# PWM_PPM_FMU3_REV_G.net
KiCad netlist of a schematic drawn in Altium Designer
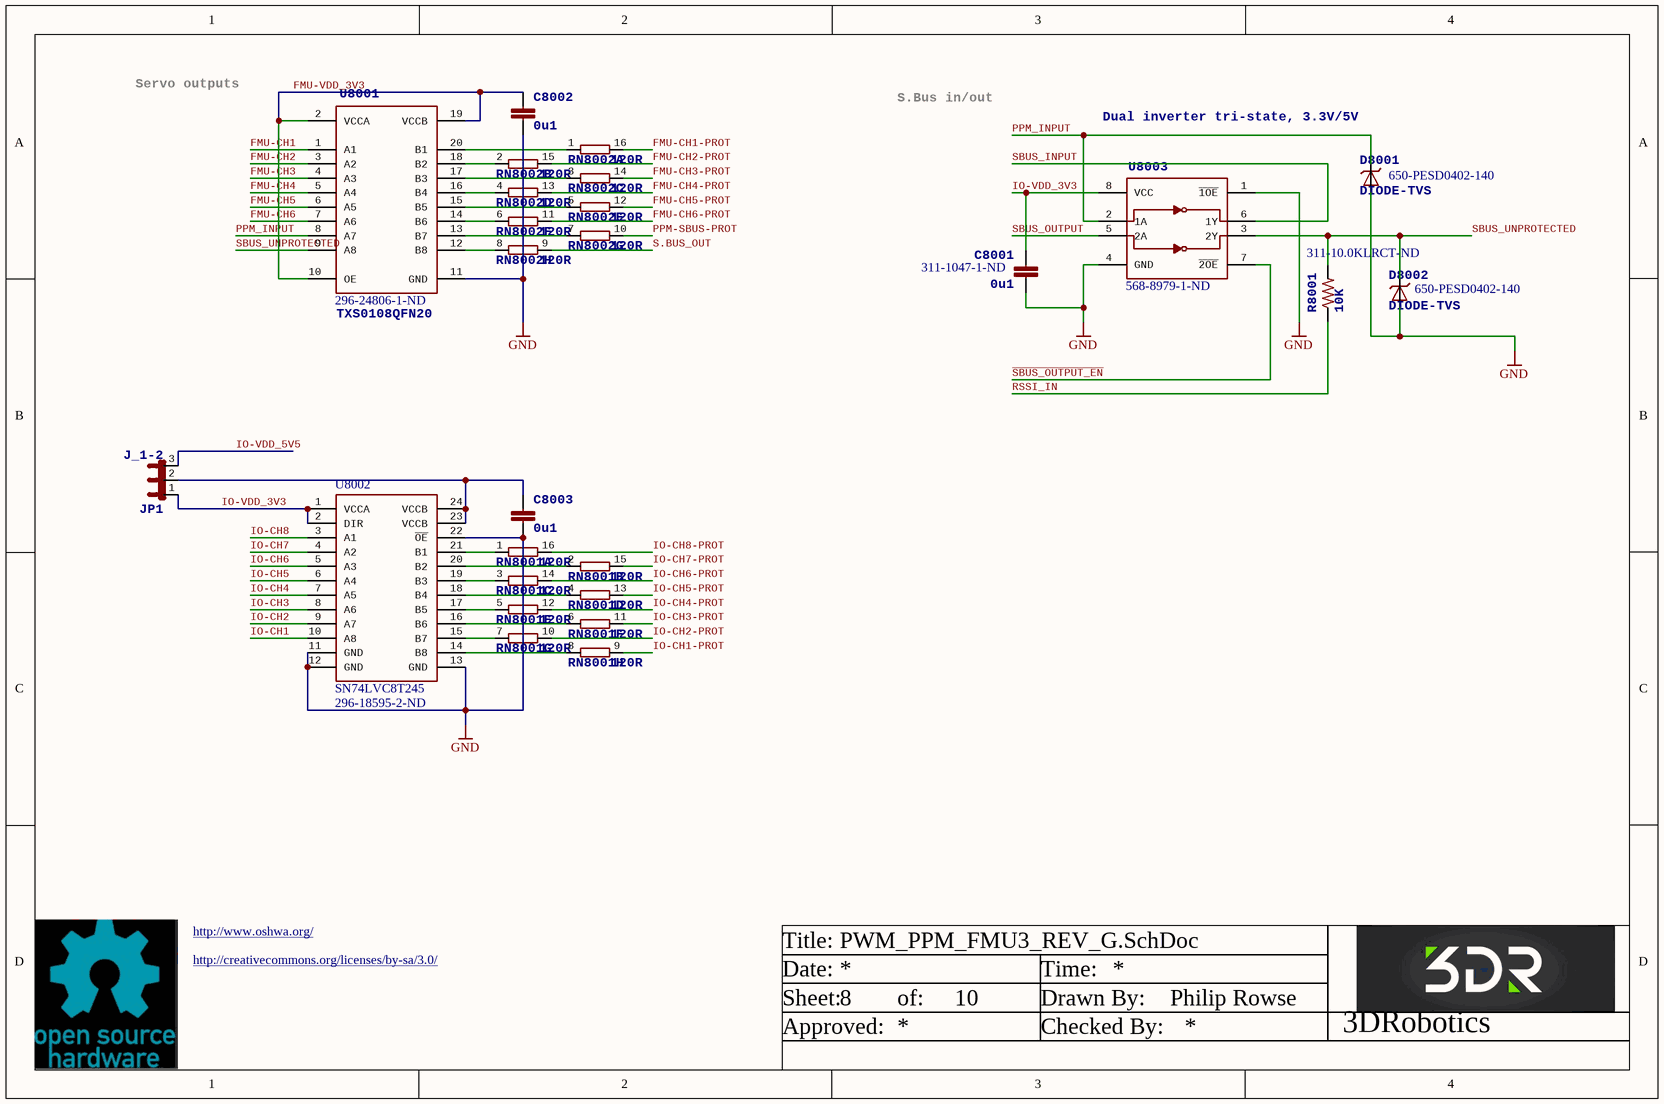
[diagram p0: PWM_PPM_FMU3_REV_G.SchDoc]

(export (version "E")
  (design (tool "Eeschema 10.0.6"))
  (components
    (comp (ref "C8001")
      (value "0u1")
      (footprint "0402-CAP")
      (description "CAP CER 0.1UF 16V Y5V 0402")
      (fields
        (field (name "PARTNO") "CC0402ZRY5V7BB104")
        (field (name "SUPPLIER PART NUMBER 1") "311-1047-1-ND")
        (field (name "3DR_PARTNO") "ECM0700")
      )
      (libsource (lib "") (part "CAP0402_1"))
    )
    (comp (ref "C8002")
      (value "0u1")
      (footprint "0402-CAP")
      (description "CAP CER 0.1UF 16V Y5V 0402")
      (fields (field (name "PARTNO") "CC0402ZRY5V7BB104") (field (name "3DR_PARTNO") "ECM0700"))
      (libsource (lib "pixhawk2") (part "CAP0402"))
    )
    (comp (ref "C8003")
      (value "0u1")
      (footprint "0402-CAP")
      (description "CAP CER 0.1UF 16V Y5V 0402")
      (fields (field (name "PARTNO") "CC0402ZRY5V7BB104") (field (name "3DR_PARTNO") "ECM0700"))
      (libsource (lib "pixhawk2") (part "CAP0402"))
    )
    (comp (ref "D8001")
      (value "DIODE-TVS")
      (footprint "0402-TVS")
      (description "TVS DIODE 14VWM 40VC 0402")
      (fields
        (field (name "SUPPLIER PART NUMBER 1") "650-PESD0402-140")
        (field (name "3DR_PARTNO") "ECM0837")
        (field (name "PARTNO") "PESD0402-140")
      )
      (libsource (lib "pixhawk2") (part "DIODE-TVS"))
    )
    (comp (ref "D8002")
      (value "DIODE-TVS")
      (footprint "0402-TVS")
      (description "TVS DIODE 14VWM 40VC 0402")
      (fields
        (field (name "SUPPLIER PART NUMBER 1") "650-PESD0402-140")
        (field (name "3DR_PARTNO") "ECM0837")
        (field (name "PARTNO") "PESD0402-140")
      )
      (libsource (lib "pixhawk2") (part "DIODE-TVS"))
    )
    (comp (ref "JP1")
      (value "J_1-2")
      (footprint "SJ_3_NO_PLACE_1-2_short")
      (libsource (lib "3DR") (part "JUMPER-31-2"))
    )
    (comp (ref "R8001")
      (value "10K")
      (footprint "0402-RES")
      (description "RES 10K OHM 1/16W 1% 0402 SMD")
      (fields
        (field (name "PARTNO") "RC0402FR-0710KL")
        (field (name "SUPPLIER PART NUMBER 1") "311-10.0KLRCT-ND")
        (field (name "3DR_PARTNO") "ECM0800")
      )
      (libsource (lib "pixhawk2") (part "RESISTOR0402-RES"))
    )
    (comp (ref "RN8001")
      (value "120R")
      (footprint "EXB2HV")
      (description "RES ARRAY 120 OHM 8 RES 1506")
      (fields (field (name "PARTNO") "EXB-2HV121JV") (field (name "3DR_PARTNO") "ECM0266"))
      (libsource (lib "pixhawk2") (part "8R-NEXB2HV-220R"))
    )
    (comp (ref "RN8002")
      (value "120R")
      (footprint "EXB2HV")
      (description "RES ARRAY 120 OHM 8 RES 1506")
      (fields (field (name "PARTNO") "EXB-2HV121JV") (field (name "3DR_PARTNO") "ECM0266"))
      (libsource (lib "pixhawk2") (part "8R-NEXB2HV-220R"))
    )
    (comp (ref "U8001")
      (value "TXS0108QFN20")
      (footprint "QFN20-RGY")
      (description "IC XLATR VOLT-LVL 8B BDIR 20QFN")
      (fields
        (field (name "SUPPLIER PART NUMBER 1") "296-24806-1-ND")
        (field (name "3DR_PARTNO") "ECM0845")
        (field (name "PARTNO") "TXS0108ERGYR")
      )
      (libsource (lib "pixhawk2") (part "TXS0108QFN20"))
    )
    (comp (ref "U8002")
      (value "SN74LVC8T245")
      (footprint "QFN20-RGY")
      (fields (field (name "SUPPLIER PART NUMBER 1") "296-18595-2-ND"))
      (libsource (lib "3DR") (part "SN74LVC8T245"))
    )
    (comp (ref "U8003")
      (value "Dual inverter tri-state, 3.3V/5V")
      (footprint "TSSOP8_SOT505-2")
      (description "IC INVERTER DUAL 4-INPUT 8TSSOP")
      (fields
        (field (name "SUPPLIER PART NUMBER 1") "568-8979-1-ND")
        (field (name "3DR_PARTNO") "ECM0817")
        (field (name "PARTNO") "74LVC2G240DP,125")
      )
      (libsource (lib "pixhawk2") (part "74LVC2G240-TSSOP-8"))
    )
  )
  (nets
    (net (code "1") (name "/FMU-CH1") (class "Default")
      (node (ref "U8001") (pin "1") (pinfunction "A1_1") (pintype "passive"))
    )
    (net (code "2") (name "/FMU-CH1-PROT") (class "Default")
      (node (ref "RN8002") (pin "16") (pinfunction "2_16") (pintype "passive"))
    )
    (net (code "3") (name "/FMU-CH2") (class "Default")
      (node (ref "U8001") (pin "3") (pinfunction "A2_3") (pintype "passive"))
    )
    (net (code "4") (name "/FMU-CH2-PROT") (class "Default")
      (node (ref "RN8002") (pin "15") (pinfunction "2_15") (pintype "passive"))
    )
    (net (code "5") (name "/FMU-CH3") (class "Default")
      (node (ref "U8001") (pin "4") (pinfunction "A3_4") (pintype "passive"))
    )
    (net (code "6") (name "/FMU-CH3-PROT") (class "Default")
      (node (ref "RN8002") (pin "14") (pinfunction "2_14") (pintype "passive"))
    )
    (net (code "7") (name "/FMU-CH4") (class "Default")
      (node (ref "U8001") (pin "5") (pinfunction "A4_5") (pintype "passive"))
    )
    (net (code "8") (name "/FMU-CH4-PROT") (class "Default")
      (node (ref "RN8002") (pin "13") (pinfunction "2_13") (pintype "passive"))
    )
    (net (code "9") (name "/FMU-CH5") (class "Default")
      (node (ref "U8001") (pin "6") (pinfunction "A5_6") (pintype "passive"))
    )
    (net (code "10") (name "/FMU-CH5-PROT") (class "Default")
      (node (ref "RN8002") (pin "12") (pinfunction "2_12") (pintype "passive"))
    )
    (net (code "11") (name "/FMU-CH6") (class "Default")
      (node (ref "U8001") (pin "7") (pinfunction "A6_7") (pintype "passive"))
    )
    (net (code "12") (name "/FMU-CH6-PROT") (class "Default")
      (node (ref "RN8002") (pin "11") (pinfunction "2_11") (pintype "passive"))
    )
    (net (code "13") (name "/FMU-VDD_3V3") (class "Default")
      (node (ref "C8002") (pin "P$1") (pinfunction "1_P$1") (pintype "passive"))
      (node (ref "U8001") (pin "10") (pinfunction "OE_10") (pintype "passive"))
      (node (ref "U8001") (pin "19") (pinfunction "VCCB_19") (pintype "passive"))
      (node (ref "U8001") (pin "2") (pinfunction "VCCA_2") (pintype "passive"))
    )
    (net (code "14") (name "/IO-CH1") (class "Default")
      (node (ref "U8002") (pin "10") (pinfunction "A8_10") (pintype "passive"))
    )
    (net (code "15") (name "/IO-CH1-PROT") (class "Default")
      (node (ref "RN8001") (pin "9") (pinfunction "2_9") (pintype "passive"))
    )
    (net (code "16") (name "/IO-CH2") (class "Default")
      (node (ref "U8002") (pin "9") (pinfunction "A7_9") (pintype "passive"))
    )
    (net (code "17") (name "/IO-CH2-PROT") (class "Default")
      (node (ref "RN8001") (pin "10") (pinfunction "2_10") (pintype "passive"))
    )
    (net (code "18") (name "/IO-CH3") (class "Default")
      (node (ref "U8002") (pin "8") (pinfunction "A6_8") (pintype "passive"))
    )
    (net (code "19") (name "/IO-CH3-PROT") (class "Default")
      (node (ref "RN8001") (pin "11") (pinfunction "2_11") (pintype "passive"))
    )
    (net (code "20") (name "/IO-CH4") (class "Default")
      (node (ref "U8002") (pin "7") (pinfunction "A5_7") (pintype "passive"))
    )
    (net (code "21") (name "/IO-CH4-PROT") (class "Default")
      (node (ref "RN8001") (pin "12") (pinfunction "2_12") (pintype "passive"))
    )
    (net (code "22") (name "/IO-CH5") (class "Default")
      (node (ref "U8002") (pin "6") (pinfunction "A4_6") (pintype "passive"))
    )
    (net (code "23") (name "/IO-CH5-PROT") (class "Default")
      (node (ref "RN8001") (pin "13") (pinfunction "2_13") (pintype "passive"))
    )
    (net (code "24") (name "/IO-CH6") (class "Default")
      (node (ref "U8002") (pin "5") (pinfunction "A3_5") (pintype "passive"))
    )
    (net (code "25") (name "/IO-CH6-PROT") (class "Default")
      (node (ref "RN8001") (pin "14") (pinfunction "2_14") (pintype "passive"))
    )
    (net (code "26") (name "/IO-CH7") (class "Default")
      (node (ref "U8002") (pin "4") (pinfunction "A2_4") (pintype "passive"))
    )
    (net (code "27") (name "/IO-CH7-PROT") (class "Default")
      (node (ref "RN8001") (pin "15") (pinfunction "2_15") (pintype "passive"))
    )
    (net (code "28") (name "/IO-CH8") (class "Default")
      (node (ref "U8002") (pin "3") (pinfunction "A1_3") (pintype "passive"))
    )
    (net (code "29") (name "/IO-CH8-PROT") (class "Default")
      (node (ref "RN8001") (pin "16") (pinfunction "2_16") (pintype "passive"))
    )
    (net (code "30") (name "/IO-VDD_3V3") (class "Default")
      (node (ref "C8001") (pin "P$1") (pinfunction "1_P$1") (pintype "passive"))
      (node (ref "JP1") (pin "1") (pinfunction "1_1") (pintype "passive"))
      (node (ref "U8002") (pin "1") (pinfunction "VCCA_1") (pintype "passive"))
      (node (ref "U8002") (pin "2") (pinfunction "DIR_2") (pintype "passive"))
      (node (ref "U8003") (pin "8") (pinfunction "VCC_8") (pintype "open_emitter"))
    )
    (net (code "31") (name "/IO-VDD_5V5") (class "Default")
      (node (ref "JP1") (pin "3") (pinfunction "3_3") (pintype "passive"))
    )
    (net (code "32") (name "/PPM-SBUS-PROT") (class "Default")
      (node (ref "RN8002") (pin "10") (pinfunction "2_10") (pintype "passive"))
    )
    (net (code "33") (name "/PPM_INPUT") (class "Default")
      (node (ref "D8001") (pin "C") (pinfunction "C_C") (pintype "passive"))
      (node (ref "U8001") (pin "8") (pinfunction "A7_8") (pintype "passive"))
      (node (ref "U8003") (pin "2") (pinfunction "1A_2") (pintype "passive"))
    )
    (net (code "34") (name "/RSSI_IN") (class "Default")
      (node (ref "R8001") (pin "P$1") (pinfunction "1_P$1") (pintype "passive"))
    )
    (net (code "35") (name "/S.BUS_OUT") (class "Default")
      (node (ref "RN8002") (pin "9") (pinfunction "2_9") (pintype "passive"))
    )
    (net (code "36") (name "/SBUS_INPUT") (class "Default")
      (node (ref "U8003") (pin "6") (pinfunction "1Y_6") (pintype "passive"))
    )
    (net (code "37") (name "/SBUS_OUTPUT") (class "Default")
      (node (ref "U8003") (pin "5") (pinfunction "2A_5") (pintype "passive"))
    )
    (net (code "38") (name "/SBUS_UNPROTECTED") (class "Default")
      (node (ref "D8002") (pin "C") (pinfunction "C_C") (pintype "passive"))
      (node (ref "R8001") (pin "P$2") (pinfunction "2_P$2") (pintype "passive"))
      (node (ref "U8001") (pin "9") (pinfunction "A8_9") (pintype "passive"))
      (node (ref "U8003") (pin "3") (pinfunction "2Y_3") (pintype "passive"))
    )
    (net (code "39") (name "/~{SBUS_OUTPUT_EN}") (class "Default")
      (node (ref "U8003") (pin "7") (pinfunction "~{2OE}_7") (pintype "passive"))
    )
    (net (code "40") (name "GND") (class "Default")
      (node (ref "C8001") (pin "P$2") (pinfunction "2_P$2") (pintype "passive"))
      (node (ref "C8002") (pin "P$2") (pinfunction "2_P$2") (pintype "passive"))
      (node (ref "C8003") (pin "P$2") (pinfunction "2_P$2") (pintype "passive"))
      (node (ref "D8001") (pin "A") (pinfunction "A_A") (pintype "passive"))
      (node (ref "D8002") (pin "A") (pinfunction "A_A") (pintype "passive"))
      (node (ref "U8001") (pin "11") (pinfunction "GND_11") (pintype "open_emitter"))
      (node (ref "U8002") (pin "11") (pinfunction "GND_11") (pintype "open_emitter"))
      (node (ref "U8002") (pin "12") (pinfunction "GND_12") (pintype "open_emitter"))
      (node (ref "U8002") (pin "13") (pinfunction "GND_13") (pintype "open_emitter"))
      (node (ref "U8002") (pin "22") (pinfunction "~{OE}_22") (pintype "passive"))
      (node (ref "U8003") (pin "1") (pinfunction "~{1OE}_1") (pintype "passive"))
      (node (ref "U8003") (pin "4") (pinfunction "GND_4") (pintype "open_emitter"))
    )
    (net (code "41") (name "Net-(C8003-1)") (class "Default")
      (node (ref "C8003") (pin "P$1") (pinfunction "1_P$1") (pintype "passive"))
      (node (ref "JP1") (pin "2") (pinfunction "2_2") (pintype "passive"))
      (node (ref "U8002") (pin "23") (pinfunction "VCCB_23") (pintype "passive"))
      (node (ref "U8002") (pin "24") (pinfunction "VCCB_24") (pintype "passive"))
    )
    (net (code "42") (name "Net-(RN8001B-1)") (class "Default")
      (node (ref "RN8001") (pin "2") (pinfunction "1_2") (pintype "passive"))
      (node (ref "U8002") (pin "20") (pinfunction "B2_20") (pintype "passive"))
    )
    (net (code "43") (name "Net-(RN8001C-1)") (class "Default")
      (node (ref "RN8001") (pin "3") (pinfunction "1_3") (pintype "passive"))
      (node (ref "U8002") (pin "19") (pinfunction "B3_19") (pintype "passive"))
    )
    (net (code "44") (name "Net-(RN8001D-1)") (class "Default")
      (node (ref "RN8001") (pin "4") (pinfunction "1_4") (pintype "passive"))
      (node (ref "U8002") (pin "18") (pinfunction "B4_18") (pintype "passive"))
    )
    (net (code "45") (name "Net-(RN8001E-1)") (class "Default")
      (node (ref "RN8001") (pin "5") (pinfunction "1_5") (pintype "passive"))
      (node (ref "U8002") (pin "17") (pinfunction "B5_17") (pintype "passive"))
    )
    (net (code "46") (name "Net-(RN8001F-1)") (class "Default")
      (node (ref "RN8001") (pin "6") (pinfunction "1_6") (pintype "passive"))
      (node (ref "U8002") (pin "16") (pinfunction "B6_16") (pintype "passive"))
    )
    (net (code "47") (name "Net-(RN8001G-1)") (class "Default")
      (node (ref "RN8001") (pin "7") (pinfunction "1_7") (pintype "passive"))
      (node (ref "U8002") (pin "15") (pinfunction "B7_15") (pintype "passive"))
    )
    (net (code "48") (name "Net-(RN8001H-1)") (class "Default")
      (node (ref "RN8001") (pin "8") (pinfunction "1_8") (pintype "passive"))
      (node (ref "U8002") (pin "14") (pinfunction "B8_14") (pintype "passive"))
    )
    (net (code "49") (name "Net-(RN8002B-1)") (class "Default")
      (node (ref "RN8002") (pin "2") (pinfunction "1_2") (pintype "passive"))
      (node (ref "U8001") (pin "18") (pinfunction "B2_18") (pintype "passive"))
    )
    (net (code "50") (name "Net-(RN8002C-1)") (class "Default")
      (node (ref "RN8002") (pin "3") (pinfunction "1_3") (pintype "passive"))
      (node (ref "U8001") (pin "17") (pinfunction "B3_17") (pintype "passive"))
    )
    (net (code "51") (name "Net-(RN8002D-1)") (class "Default")
      (node (ref "RN8002") (pin "4") (pinfunction "1_4") (pintype "passive"))
      (node (ref "U8001") (pin "16") (pinfunction "B4_16") (pintype "passive"))
    )
    (net (code "52") (name "Net-(RN8002E-1)") (class "Default")
      (node (ref "RN8002") (pin "5") (pinfunction "1_5") (pintype "passive"))
      (node (ref "U8001") (pin "15") (pinfunction "B5_15") (pintype "passive"))
    )
    (net (code "53") (name "Net-(RN8002F-1)") (class "Default")
      (node (ref "RN8002") (pin "6") (pinfunction "1_6") (pintype "passive"))
      (node (ref "U8001") (pin "14") (pinfunction "B6_14") (pintype "passive"))
    )
    (net (code "54") (name "Net-(RN8002G-1)") (class "Default")
      (node (ref "RN8002") (pin "7") (pinfunction "1_7") (pintype "passive"))
      (node (ref "U8001") (pin "13") (pinfunction "B7_13") (pintype "passive"))
    )
    (net (code "55") (name "Net-(RN8002H-1)") (class "Default")
      (node (ref "RN8002") (pin "8") (pinfunction "1_8") (pintype "passive"))
      (node (ref "U8001") (pin "12") (pinfunction "B8_12") (pintype "passive"))
    )
    (net (code "56") (name "Net-(U8001-B1)") (class "Default")
      (node (ref "RN8002") (pin "1") (pinfunction "1_1") (pintype "passive"))
      (node (ref "U8001") (pin "20") (pinfunction "B1_20") (pintype "passive"))
    )
    (net (code "57") (name "Net-(U8002-B1)") (class "Default")
      (node (ref "RN8001") (pin "1") (pinfunction "1_1") (pintype "passive"))
      (node (ref "U8002") (pin "21") (pinfunction "B1_21") (pintype "passive"))
    )
  )
)
